# Secondary_Board_2_0.net
KiCad netlist of a schematic drawn in EAGLE
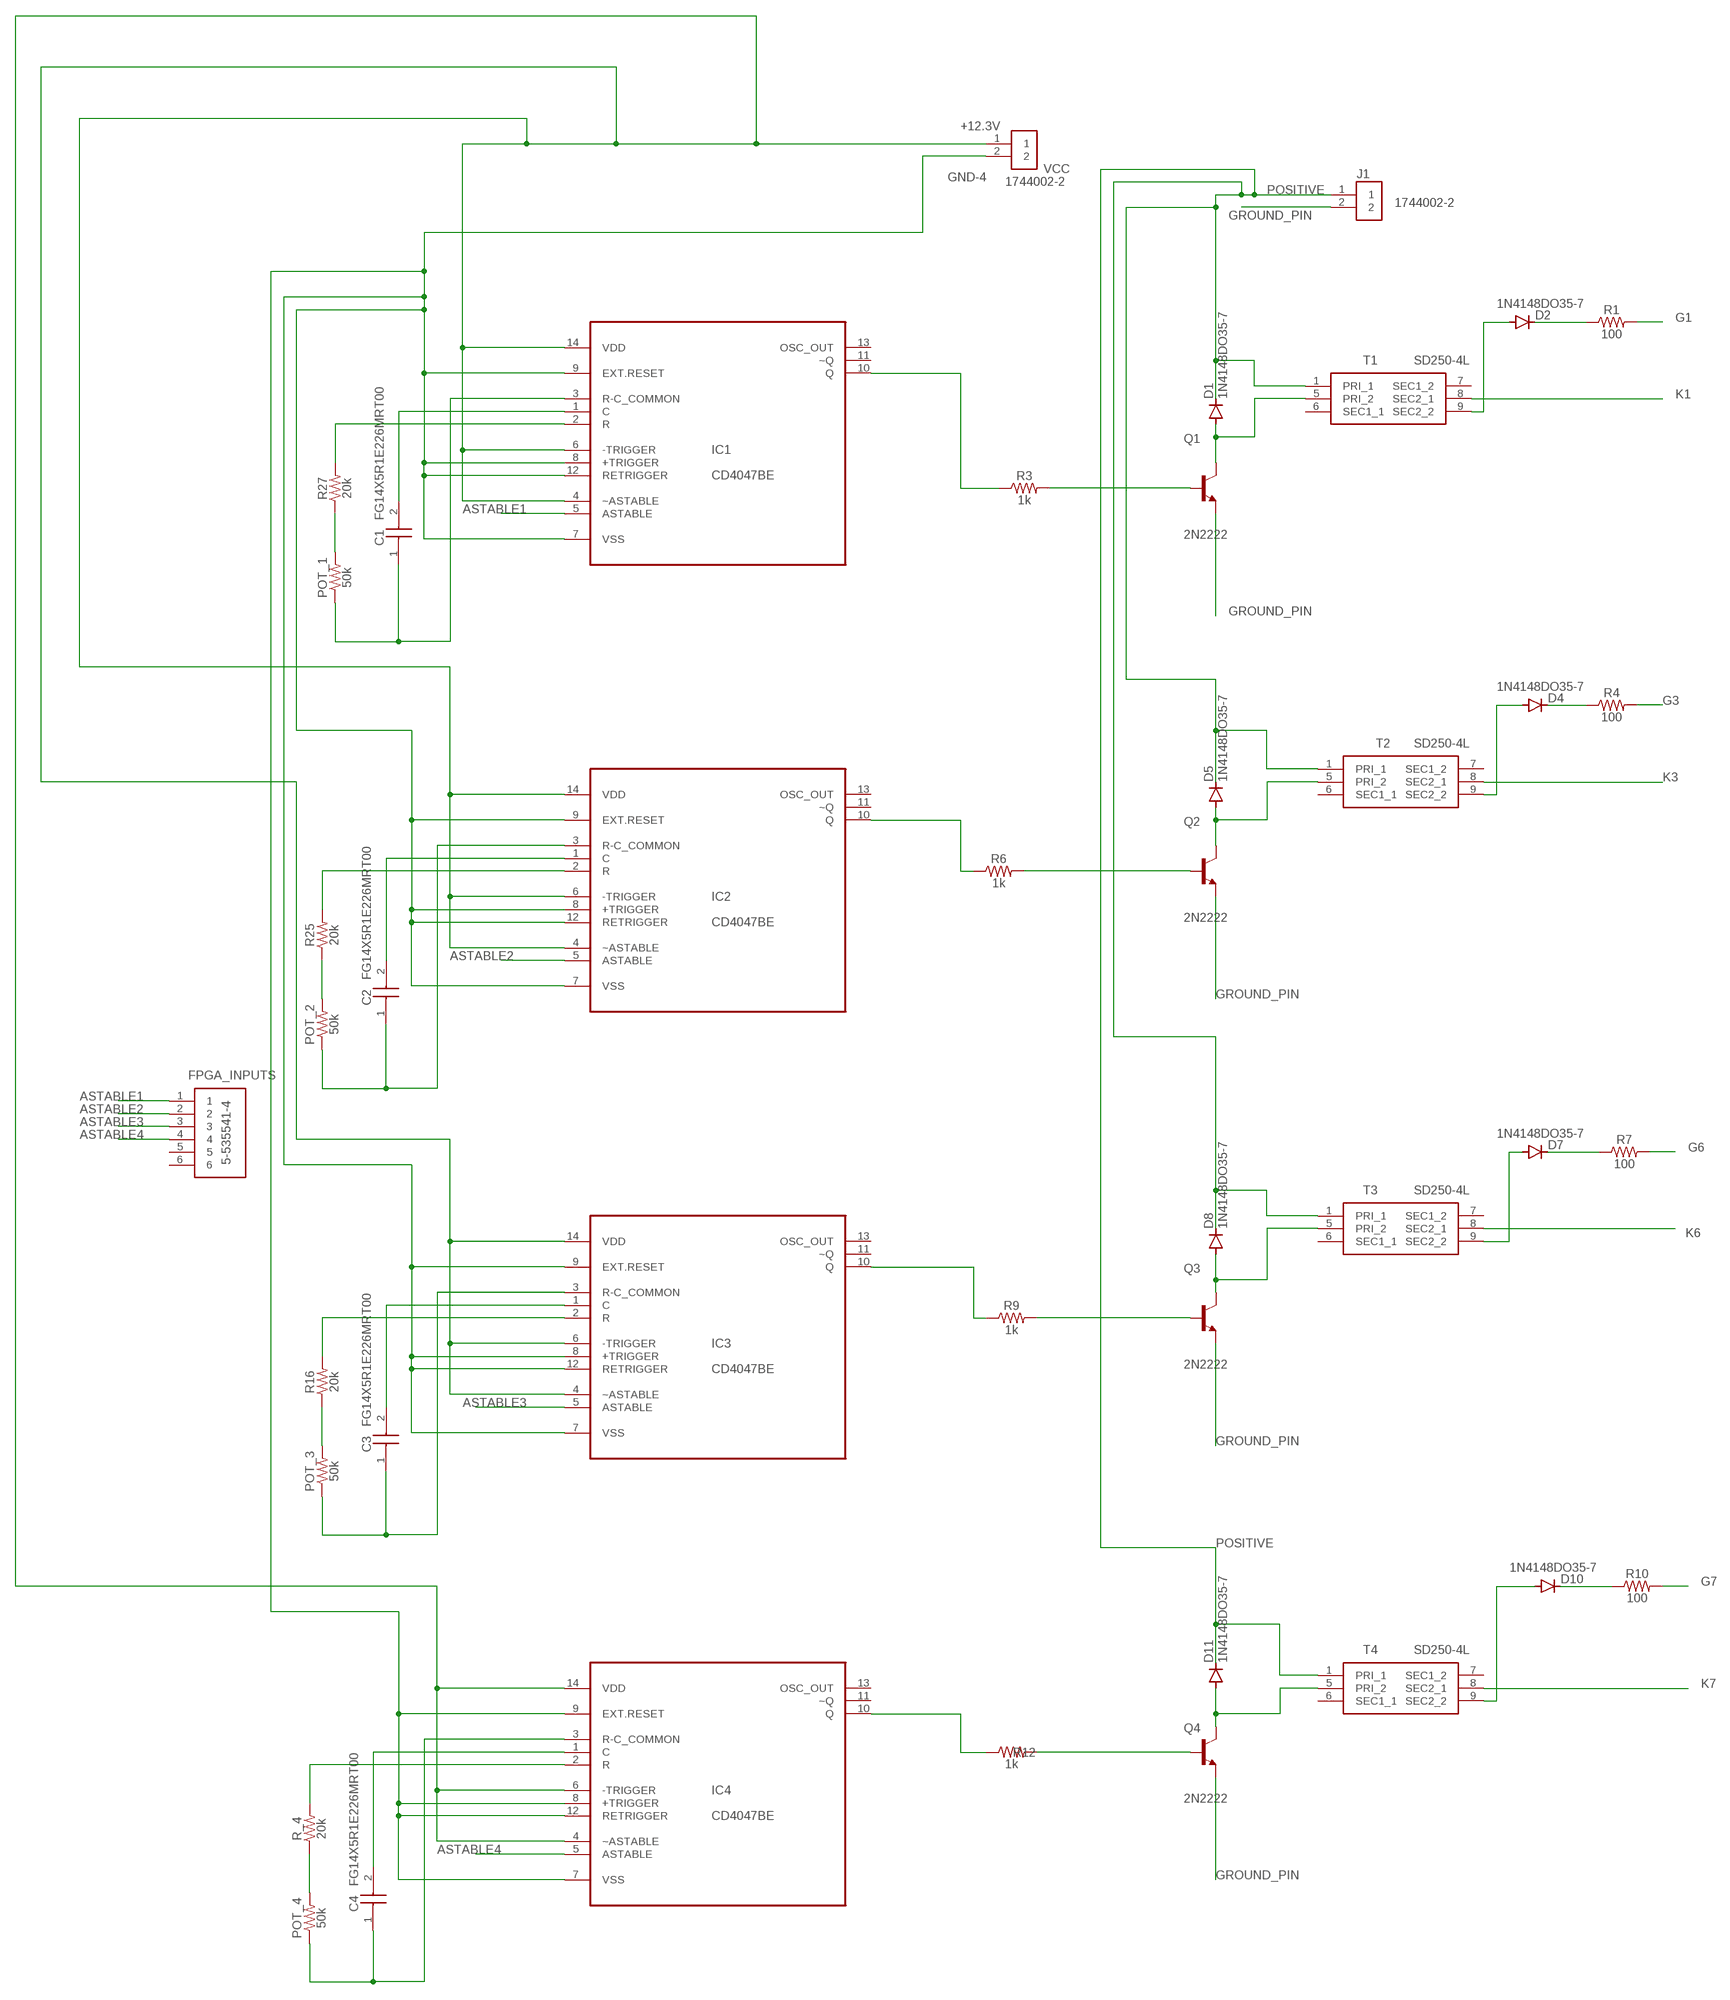
[diagram p0: schematic, sheet 1, part 1 of 2]
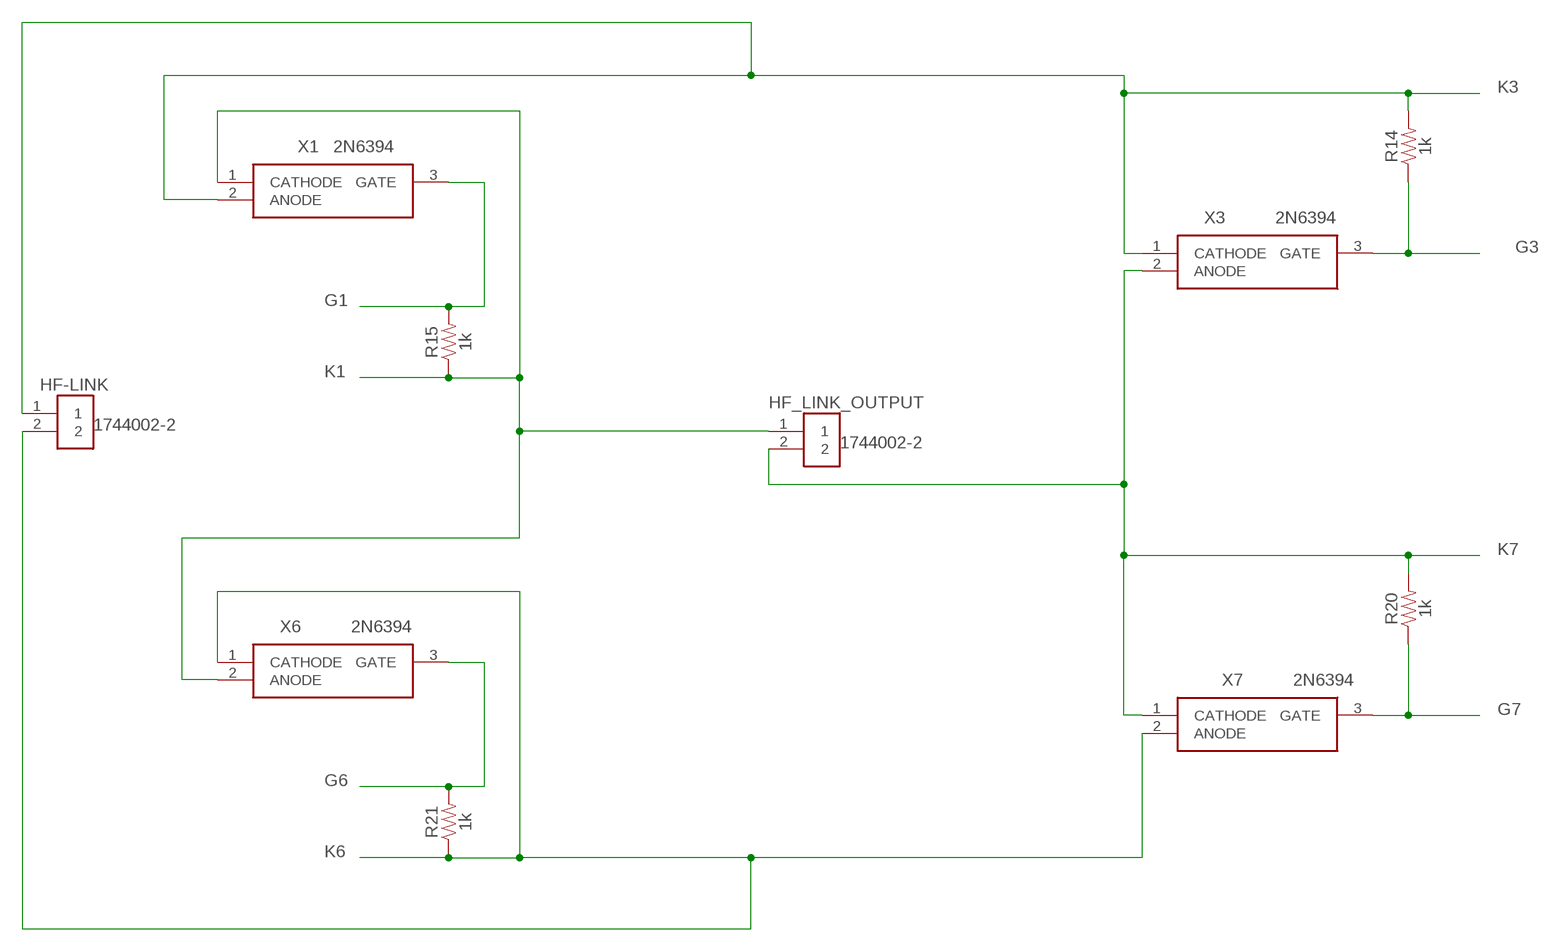
[diagram p1: schematic, sheet 1, part 2 of 2]

(export (version "E")
  (design (tool "Eeschema 10.0.6"))
  (components
    (comp (ref "C1")
      (value "FG14X5R1E226MRT00")
      (footprint "eagle-import:CAPPRD550W50D395H550")
      (libsource (lib "eagle-import") (part "FG14X5R1E226MRT00"))
    )
    (comp (ref "C2")
      (value "FG14X5R1E226MRT00")
      (footprint "eagle-import:CAPPRD550W50D395H550")
      (libsource (lib "eagle-import") (part "FG14X5R1E226MRT00"))
    )
    (comp (ref "C3")
      (value "FG14X5R1E226MRT00")
      (footprint "eagle-import:CAPPRD550W50D395H550")
      (libsource (lib "eagle-import") (part "FG14X5R1E226MRT00"))
    )
    (comp (ref "C4")
      (value "FG14X5R1E226MRT00")
      (footprint "eagle-import:CAPPRD550W50D395H550")
      (libsource (lib "eagle-import") (part "FG14X5R1E226MRT00"))
    )
    (comp (ref "D1")
      (value "1N4148DO35-7")
      (footprint "eagle-import:DO35-7")
      (libsource (lib "eagle-import") (part "1N4148DO35-7"))
    )
    (comp (ref "D2")
      (value "1N4148DO35-7")
      (footprint "eagle-import:DO35-7")
      (libsource (lib "eagle-import") (part "1N4148DO35-7"))
    )
    (comp (ref "D4")
      (value "1N4148DO35-7")
      (footprint "eagle-import:DO35-7")
      (libsource (lib "eagle-import") (part "1N4148DO35-7"))
    )
    (comp (ref "D5")
      (value "1N4148DO35-7")
      (footprint "eagle-import:DO35-7")
      (libsource (lib "eagle-import") (part "1N4148DO35-7"))
    )
    (comp (ref "D7")
      (value "1N4148DO35-7")
      (footprint "eagle-import:DO35-7")
      (libsource (lib "eagle-import") (part "1N4148DO35-7"))
    )
    (comp (ref "D8")
      (value "1N4148DO35-7")
      (footprint "eagle-import:DO35-7")
      (libsource (lib "eagle-import") (part "1N4148DO35-7"))
    )
    (comp (ref "D10")
      (value "1N4148DO35-7")
      (footprint "eagle-import:DO35-7")
      (libsource (lib "eagle-import") (part "1N4148DO35-7"))
    )
    (comp (ref "D11")
      (value "1N4148DO35-7")
      (footprint "eagle-import:DO35-7")
      (libsource (lib "eagle-import") (part "1N4148DO35-7"))
    )
    (comp (ref "FPGA_INPUTS")
      (value "5-535541-4")
      (footprint "eagle-import:SHDR6W76P0X254_1X6_1524X356X62")
      (fields (field (name "MOUSER_PART_NUMBER") "571-5-535541-4"))
      (libsource (lib "eagle-import") (part "5-535541-4"))
    )
    (comp (ref "HF-LINK")
      (value "1744002-2")
      (footprint "eagle-import:CONN_1744002-2")
      (fields (field (name "MF") "TE Connectivity"))
      (libsource (lib "eagle-import") (part "1744002-2"))
    )
    (comp (ref "HF_LINK_OUTPUT")
      (value "1744002-2")
      (footprint "eagle-import:CONN_1744002-2")
      (fields (field (name "MF") "TE Connectivity"))
      (libsource (lib "eagle-import") (part "1744002-2"))
    )
    (comp (ref "IC1")
      (value "CD4047BE")
      (footprint "eagle-import:DIP254P762X508-14")
      (fields (field (name "MF") "Texas Instruments"))
      (libsource (lib "eagle-import") (part "CD4047BE"))
    )
    (comp (ref "IC2")
      (value "CD4047BE")
      (footprint "eagle-import:DIP254P762X508-14")
      (fields (field (name "MF") "Texas Instruments"))
      (libsource (lib "eagle-import") (part "CD4047BE"))
    )
    (comp (ref "IC3")
      (value "CD4047BE")
      (footprint "eagle-import:DIP254P762X508-14")
      (fields (field (name "MF") "Texas Instruments"))
      (libsource (lib "eagle-import") (part "CD4047BE"))
    )
    (comp (ref "IC4")
      (value "CD4047BE")
      (footprint "eagle-import:DIP254P762X508-14")
      (fields (field (name "MF") "Texas Instruments"))
      (libsource (lib "eagle-import") (part "CD4047BE"))
    )
    (comp (ref "J1")
      (value "1744002-2")
      (footprint "eagle-import:CONN_1744002-2")
      (fields (field (name "MF") "TE Connectivity"))
      (libsource (lib "eagle-import") (part "1744002-2"))
    )
    (comp (ref "POT_1")
      (value "50k")
      (footprint "eagle-import:AXIAL-0.3")
      (libsource (lib "eagle-import") (part "1KOHM-HORIZ-1/4W-1%"))
    )
    (comp (ref "POT_2")
      (value "50k")
      (footprint "eagle-import:AXIAL-0.3")
      (libsource (lib "eagle-import") (part "1KOHM-HORIZ-1/4W-1%"))
    )
    (comp (ref "POT_3")
      (value "50k")
      (footprint "eagle-import:AXIAL-0.3")
      (libsource (lib "eagle-import") (part "1KOHM-HORIZ-1/4W-1%"))
    )
    (comp (ref "POT_4")
      (value "50k")
      (footprint "eagle-import:AXIAL-0.3")
      (libsource (lib "eagle-import") (part "1KOHM-HORIZ-1/4W-1%"))
    )
    (comp (ref "Q1")
      (value "2N2222")
      (footprint "eagle-import:TO127P584H533-3")
      (fields (field (name "MF") "Central Semiconductor"))
      (libsource (lib "eagle-import") (part "2N2222"))
    )
    (comp (ref "Q2")
      (value "2N2222")
      (footprint "eagle-import:TO127P584H533-3")
      (fields (field (name "MF") "Central Semiconductor"))
      (libsource (lib "eagle-import") (part "2N2222"))
    )
    (comp (ref "Q3")
      (value "2N2222")
      (footprint "eagle-import:TO127P584H533-3")
      (fields (field (name "MF") "Central Semiconductor"))
      (libsource (lib "eagle-import") (part "2N2222"))
    )
    (comp (ref "Q4")
      (value "2N2222")
      (footprint "eagle-import:TO127P584H533-3")
      (fields (field (name "MF") "Central Semiconductor"))
      (libsource (lib "eagle-import") (part "2N2222"))
    )
    (comp (ref "R1")
      (value "100")
      (footprint "eagle-import:AXIAL-0.3")
      (libsource (lib "eagle-import") (part "100OHM-HORIZ-1/4W-1%"))
    )
    (comp (ref "R3")
      (value "1k")
      (footprint "eagle-import:AXIAL-0.3")
      (libsource (lib "eagle-import") (part "1KOHM-HORIZ-1/4W-1%"))
    )
    (comp (ref "R4")
      (value "100")
      (footprint "eagle-import:AXIAL-0.3")
      (libsource (lib "eagle-import") (part "100OHM-HORIZ-1/4W-1%"))
    )
    (comp (ref "R6")
      (value "1k")
      (footprint "eagle-import:AXIAL-0.3")
      (libsource (lib "eagle-import") (part "1KOHM-HORIZ-1/4W-1%"))
    )
    (comp (ref "R7")
      (value "100")
      (footprint "eagle-import:AXIAL-0.3")
      (libsource (lib "eagle-import") (part "100OHM-HORIZ-1/4W-1%"))
    )
    (comp (ref "R9")
      (value "1k")
      (footprint "eagle-import:AXIAL-0.3")
      (libsource (lib "eagle-import") (part "1KOHM-HORIZ-1/4W-1%"))
    )
    (comp (ref "R10")
      (value "100")
      (footprint "eagle-import:AXIAL-0.3")
      (libsource (lib "eagle-import") (part "100OHM-HORIZ-1/4W-1%"))
    )
    (comp (ref "R12")
      (value "1k")
      (footprint "eagle-import:AXIAL-0.3")
      (libsource (lib "eagle-import") (part "1KOHM-HORIZ-1/4W-1%"))
    )
    (comp (ref "R14")
      (value "1k")
      (footprint "eagle-import:AXIAL-0.3")
      (libsource (lib "eagle-import") (part "1KOHM-HORIZ-1/4W-1%"))
    )
    (comp (ref "R15")
      (value "1k")
      (footprint "eagle-import:AXIAL-0.3")
      (libsource (lib "eagle-import") (part "1KOHM-HORIZ-1/4W-1%"))
    )
    (comp (ref "R16")
      (value "20k")
      (footprint "eagle-import:AXIAL-0.3")
      (libsource (lib "eagle-import") (part "1KOHM-HORIZ-1/4W-1%"))
    )
    (comp (ref "R20")
      (value "1k")
      (footprint "eagle-import:AXIAL-0.3")
      (libsource (lib "eagle-import") (part "1KOHM-HORIZ-1/4W-1%"))
    )
    (comp (ref "R21")
      (value "1k")
      (footprint "eagle-import:AXIAL-0.3")
      (libsource (lib "eagle-import") (part "1KOHM-HORIZ-1/4W-1%"))
    )
    (comp (ref "R25")
      (value "20k")
      (footprint "eagle-import:AXIAL-0.3")
      (libsource (lib "eagle-import") (part "1KOHM-HORIZ-1/4W-1%"))
    )
    (comp (ref "R27")
      (value "20k")
      (footprint "eagle-import:AXIAL-0.3")
      (libsource (lib "eagle-import") (part "1KOHM-HORIZ-1/4W-1%"))
    )
    (comp (ref "R_4")
      (value "20k")
      (footprint "eagle-import:AXIAL-0.3")
      (libsource (lib "eagle-import") (part "1KOHM-HORIZ-1/4W-1%"))
    )
    (comp (ref "T1")
      (value "SD250-4L")
      (footprint "eagle-import:SD2504L")
      (libsource (lib "eagle-import") (part "SD250-4L"))
    )
    (comp (ref "T2")
      (value "SD250-4L")
      (footprint "eagle-import:SD2504L")
      (libsource (lib "eagle-import") (part "SD250-4L"))
    )
    (comp (ref "T3")
      (value "SD250-4L")
      (footprint "eagle-import:SD2504L")
      (libsource (lib "eagle-import") (part "SD250-4L"))
    )
    (comp (ref "T4")
      (value "SD250-4L")
      (footprint "eagle-import:SD2504L")
      (libsource (lib "eagle-import") (part "SD250-4L"))
    )
    (comp (ref "VCC")
      (value "1744002-2")
      (footprint "eagle-import:CONN_1744002-2")
      (fields (field (name "MF") "TE Connectivity"))
      (libsource (lib "eagle-import") (part "1744002-2"))
    )
    (comp (ref "X1")
      (value "2N6394")
      (footprint "eagle-import:TO254P482X997X2018-3P")
      (fields (field (name "MOUSER_PART_NUMBER") "863-2N6394"))
      (libsource (lib "eagle-import") (part "2N6394"))
    )
    (comp (ref "X3")
      (value "2N6394")
      (footprint "eagle-import:TO254P482X997X2018-3P")
      (fields (field (name "MOUSER_PART_NUMBER") "863-2N6394"))
      (libsource (lib "eagle-import") (part "2N6394"))
    )
    (comp (ref "X6")
      (value "2N6394")
      (footprint "eagle-import:TO254P482X997X2018-3P")
      (fields (field (name "MOUSER_PART_NUMBER") "863-2N6394"))
      (libsource (lib "eagle-import") (part "2N6394"))
    )
    (comp (ref "X7")
      (value "2N6394")
      (footprint "eagle-import:TO254P482X997X2018-3P")
      (fields (field (name "MOUSER_PART_NUMBER") "863-2N6394"))
      (libsource (lib "eagle-import") (part "2N6394"))
    )
  )
  (nets
    (net (code "1") (name "/+12.3V") (class "Default")
      (node (ref "IC1") (pin "14") (pinfunction "VDD_14") (pintype "power_in"))
      (node (ref "IC1") (pin "4") (pinfunction "~{ASTABLE}_4") (pintype "input"))
      (node (ref "IC1") (pin "6") (pinfunction "-TRIGGER_6") (pintype "power_in"))
      (node (ref "IC2") (pin "14") (pinfunction "VDD_14") (pintype "power_in"))
      (node (ref "IC2") (pin "4") (pinfunction "~{ASTABLE}_4") (pintype "input"))
      (node (ref "IC2") (pin "6") (pinfunction "-TRIGGER_6") (pintype "power_in"))
      (node (ref "IC3") (pin "14") (pinfunction "VDD_14") (pintype "power_in"))
      (node (ref "IC3") (pin "4") (pinfunction "~{ASTABLE}_4") (pintype "input"))
      (node (ref "IC3") (pin "6") (pinfunction "-TRIGGER_6") (pintype "power_in"))
      (node (ref "IC4") (pin "14") (pinfunction "VDD_14") (pintype "power_in"))
      (node (ref "IC4") (pin "4") (pinfunction "~{ASTABLE}_4") (pintype "input"))
      (node (ref "IC4") (pin "6") (pinfunction "-TRIGGER_6") (pintype "power_in"))
      (node (ref "VCC") (pin "1") (pinfunction "1_1") (pintype "passive"))
    )
    (net (code "2") (name "/ASTABLE1") (class "Default")
      (node (ref "FPGA_INPUTS") (pin "1") (pinfunction "1_1") (pintype "bidirectional"))
      (node (ref "IC1") (pin "5") (pinfunction "ASTABLE_5") (pintype "input"))
    )
    (net (code "3") (name "/ASTABLE2") (class "Default")
      (node (ref "FPGA_INPUTS") (pin "2") (pinfunction "2_2") (pintype "bidirectional"))
      (node (ref "IC2") (pin "5") (pinfunction "ASTABLE_5") (pintype "input"))
    )
    (net (code "4") (name "/ASTABLE3") (class "Default")
      (node (ref "FPGA_INPUTS") (pin "3") (pinfunction "3_3") (pintype "bidirectional"))
      (node (ref "IC3") (pin "5") (pinfunction "ASTABLE_5") (pintype "input"))
    )
    (net (code "5") (name "/ASTABLE4") (class "Default")
      (node (ref "FPGA_INPUTS") (pin "4") (pinfunction "4_4") (pintype "bidirectional"))
      (node (ref "IC4") (pin "5") (pinfunction "ASTABLE_5") (pintype "input"))
    )
    (net (code "6") (name "/G1") (class "Default")
      (node (ref "R1") (pin "P$2") (pinfunction "2_P$2") (pintype "passive"))
      (node (ref "R15") (pin "P$2") (pinfunction "2_P$2") (pintype "passive"))
      (node (ref "X1") (pin "3") (pinfunction "GATE_3") (pintype "bidirectional"))
    )
    (net (code "7") (name "/G3") (class "Default")
      (node (ref "R14") (pin "P$1") (pinfunction "1_P$1") (pintype "passive"))
      (node (ref "R4") (pin "P$2") (pinfunction "2_P$2") (pintype "passive"))
      (node (ref "X3") (pin "3") (pinfunction "GATE_3") (pintype "bidirectional"))
    )
    (net (code "8") (name "/G6") (class "Default")
      (node (ref "R21") (pin "P$2") (pinfunction "2_P$2") (pintype "passive"))
      (node (ref "R7") (pin "P$2") (pinfunction "2_P$2") (pintype "passive"))
      (node (ref "X6") (pin "3") (pinfunction "GATE_3") (pintype "bidirectional"))
    )
    (net (code "9") (name "/G7") (class "Default")
      (node (ref "R10") (pin "P$2") (pinfunction "2_P$2") (pintype "passive"))
      (node (ref "R20") (pin "P$1") (pinfunction "1_P$1") (pintype "passive"))
      (node (ref "X7") (pin "3") (pinfunction "GATE_3") (pintype "bidirectional"))
    )
    (net (code "10") (name "/GND-4") (class "Default")
      (node (ref "IC1") (pin "12") (pinfunction "RETRIGGER_12") (pintype "input"))
      (node (ref "IC1") (pin "7") (pinfunction "VSS_7") (pintype "power_in"))
      (node (ref "IC1") (pin "8") (pinfunction "+TRIGGER_8") (pintype "input"))
      (node (ref "IC1") (pin "9") (pinfunction "EXT.RESET_9") (pintype "input"))
      (node (ref "IC2") (pin "12") (pinfunction "RETRIGGER_12") (pintype "input"))
      (node (ref "IC2") (pin "7") (pinfunction "VSS_7") (pintype "power_in"))
      (node (ref "IC2") (pin "8") (pinfunction "+TRIGGER_8") (pintype "input"))
      (node (ref "IC2") (pin "9") (pinfunction "EXT.RESET_9") (pintype "input"))
      (node (ref "IC3") (pin "12") (pinfunction "RETRIGGER_12") (pintype "input"))
      (node (ref "IC3") (pin "7") (pinfunction "VSS_7") (pintype "power_in"))
      (node (ref "IC3") (pin "8") (pinfunction "+TRIGGER_8") (pintype "input"))
      (node (ref "IC3") (pin "9") (pinfunction "EXT.RESET_9") (pintype "input"))
      (node (ref "IC4") (pin "12") (pinfunction "RETRIGGER_12") (pintype "input"))
      (node (ref "IC4") (pin "7") (pinfunction "VSS_7") (pintype "power_in"))
      (node (ref "IC4") (pin "8") (pinfunction "+TRIGGER_8") (pintype "input"))
      (node (ref "IC4") (pin "9") (pinfunction "EXT.RESET_9") (pintype "input"))
      (node (ref "VCC") (pin "2") (pinfunction "2_2") (pintype "passive"))
    )
    (net (code "11") (name "/GROUND_PIN") (class "Default")
      (node (ref "J1") (pin "2") (pinfunction "2_2") (pintype "passive"))
      (node (ref "Q1") (pin "1") (pinfunction "E_1") (pintype "passive"))
      (node (ref "Q2") (pin "1") (pinfunction "E_1") (pintype "passive"))
      (node (ref "Q3") (pin "1") (pinfunction "E_1") (pintype "passive"))
      (node (ref "Q4") (pin "1") (pinfunction "E_1") (pintype "passive"))
    )
    (net (code "12") (name "/K1") (class "Default")
      (node (ref "HF_LINK_OUTPUT") (pin "1") (pinfunction "1_1") (pintype "passive"))
      (node (ref "R15") (pin "P$1") (pinfunction "1_P$1") (pintype "passive"))
      (node (ref "T1") (pin "8") (pinfunction "SEC2_1_8") (pintype "bidirectional"))
      (node (ref "X1") (pin "1") (pinfunction "CATHODE_1") (pintype "bidirectional"))
      (node (ref "X6") (pin "2") (pinfunction "ANODE_2") (pintype "bidirectional"))
    )
    (net (code "13") (name "/K3") (class "Default")
      (node (ref "HF-LINK") (pin "1") (pinfunction "1_1") (pintype "passive"))
      (node (ref "R14") (pin "P$2") (pinfunction "2_P$2") (pintype "passive"))
      (node (ref "T2") (pin "8") (pinfunction "SEC2_1_8") (pintype "bidirectional"))
      (node (ref "X1") (pin "2") (pinfunction "ANODE_2") (pintype "bidirectional"))
      (node (ref "X3") (pin "1") (pinfunction "CATHODE_1") (pintype "bidirectional"))
    )
    (net (code "14") (name "/K6") (class "Default")
      (node (ref "HF-LINK") (pin "2") (pinfunction "2_2") (pintype "passive"))
      (node (ref "R21") (pin "P$1") (pinfunction "1_P$1") (pintype "passive"))
      (node (ref "T3") (pin "8") (pinfunction "SEC2_1_8") (pintype "bidirectional"))
      (node (ref "X6") (pin "1") (pinfunction "CATHODE_1") (pintype "bidirectional"))
      (node (ref "X7") (pin "2") (pinfunction "ANODE_2") (pintype "bidirectional"))
    )
    (net (code "15") (name "/K7") (class "Default")
      (node (ref "HF_LINK_OUTPUT") (pin "2") (pinfunction "2_2") (pintype "passive"))
      (node (ref "R20") (pin "P$2") (pinfunction "2_P$2") (pintype "passive"))
      (node (ref "T4") (pin "8") (pinfunction "SEC2_1_8") (pintype "bidirectional"))
      (node (ref "X3") (pin "2") (pinfunction "ANODE_2") (pintype "bidirectional"))
      (node (ref "X7") (pin "1") (pinfunction "CATHODE_1") (pintype "bidirectional"))
    )
    (net (code "16") (name "/POSITIVE") (class "Default")
      (node (ref "D1") (pin "C") (pinfunction "C_C") (pintype "passive"))
      (node (ref "D11") (pin "C") (pinfunction "C_C") (pintype "passive"))
      (node (ref "D5") (pin "C") (pinfunction "C_C") (pintype "passive"))
      (node (ref "D8") (pin "C") (pinfunction "C_C") (pintype "passive"))
      (node (ref "J1") (pin "1") (pinfunction "1_1") (pintype "passive"))
      (node (ref "T1") (pin "1") (pinfunction "PRI_1_1") (pintype "bidirectional"))
      (node (ref "T2") (pin "1") (pinfunction "PRI_1_1") (pintype "bidirectional"))
      (node (ref "T3") (pin "1") (pinfunction "PRI_1_1") (pintype "bidirectional"))
      (node (ref "T4") (pin "1") (pinfunction "PRI_1_1") (pintype "bidirectional"))
    )
    (net (code "17") (name "Net-(C1-+)") (class "Default")
      (node (ref "C1") (pin "1") (pinfunction "+_1") (pintype "bidirectional"))
      (node (ref "IC1") (pin "3") (pinfunction "R-C_COMMON_3") (pintype "input"))
      (node (ref "POT_1") (pin "P$1") (pinfunction "1_P$1") (pintype "passive"))
    )
    (net (code "18") (name "Net-(C1--)") (class "Default")
      (node (ref "C1") (pin "2") (pinfunction "-_2") (pintype "bidirectional"))
      (node (ref "IC1") (pin "1") (pinfunction "C_1") (pintype "input"))
    )
    (net (code "19") (name "Net-(C2-+)") (class "Default")
      (node (ref "C2") (pin "1") (pinfunction "+_1") (pintype "bidirectional"))
      (node (ref "IC2") (pin "3") (pinfunction "R-C_COMMON_3") (pintype "input"))
      (node (ref "POT_2") (pin "P$1") (pinfunction "1_P$1") (pintype "passive"))
    )
    (net (code "20") (name "Net-(C2--)") (class "Default")
      (node (ref "C2") (pin "2") (pinfunction "-_2") (pintype "bidirectional"))
      (node (ref "IC2") (pin "1") (pinfunction "C_1") (pintype "input"))
    )
    (net (code "21") (name "Net-(C3-+)") (class "Default")
      (node (ref "C3") (pin "1") (pinfunction "+_1") (pintype "bidirectional"))
      (node (ref "IC3") (pin "3") (pinfunction "R-C_COMMON_3") (pintype "input"))
      (node (ref "POT_3") (pin "P$1") (pinfunction "1_P$1") (pintype "passive"))
    )
    (net (code "22") (name "Net-(C3--)") (class "Default")
      (node (ref "C3") (pin "2") (pinfunction "-_2") (pintype "bidirectional"))
      (node (ref "IC3") (pin "1") (pinfunction "C_1") (pintype "input"))
    )
    (net (code "23") (name "Net-(C4-+)") (class "Default")
      (node (ref "C4") (pin "1") (pinfunction "+_1") (pintype "bidirectional"))
      (node (ref "IC4") (pin "3") (pinfunction "R-C_COMMON_3") (pintype "input"))
      (node (ref "POT_4") (pin "P$1") (pinfunction "1_P$1") (pintype "passive"))
    )
    (net (code "24") (name "Net-(C4--)") (class "Default")
      (node (ref "C4") (pin "2") (pinfunction "-_2") (pintype "bidirectional"))
      (node (ref "IC4") (pin "1") (pinfunction "C_1") (pintype "input"))
    )
    (net (code "25") (name "Net-(IC1-Q)") (class "Default")
      (node (ref "IC1") (pin "10") (pinfunction "Q_10") (pintype "output"))
      (node (ref "R3") (pin "P$1") (pinfunction "1_P$1") (pintype "passive"))
    )
    (net (code "26") (name "Net-(IC1-R)") (class "Default")
      (node (ref "IC1") (pin "2") (pinfunction "R_2") (pintype "input"))
      (node (ref "R27") (pin "P$2") (pinfunction "2_P$2") (pintype "passive"))
    )
    (net (code "27") (name "Net-(IC2-Q)") (class "Default")
      (node (ref "IC2") (pin "10") (pinfunction "Q_10") (pintype "output"))
      (node (ref "R6") (pin "P$1") (pinfunction "1_P$1") (pintype "passive"))
    )
    (net (code "28") (name "Net-(IC2-R)") (class "Default")
      (node (ref "IC2") (pin "2") (pinfunction "R_2") (pintype "input"))
      (node (ref "R25") (pin "P$2") (pinfunction "2_P$2") (pintype "passive"))
    )
    (net (code "29") (name "Net-(IC3-Q)") (class "Default")
      (node (ref "IC3") (pin "10") (pinfunction "Q_10") (pintype "output"))
      (node (ref "R9") (pin "P$1") (pinfunction "1_P$1") (pintype "passive"))
    )
    (net (code "30") (name "Net-(IC3-R)") (class "Default")
      (node (ref "IC3") (pin "2") (pinfunction "R_2") (pintype "input"))
      (node (ref "R16") (pin "P$2") (pinfunction "2_P$2") (pintype "passive"))
    )
    (net (code "31") (name "Net-(IC4-Q)") (class "Default")
      (node (ref "IC4") (pin "10") (pinfunction "Q_10") (pintype "output"))
      (node (ref "R12") (pin "P$1") (pinfunction "1_P$1") (pintype "passive"))
    )
    (net (code "32") (name "Net-(IC4-R)") (class "Default")
      (node (ref "IC4") (pin "2") (pinfunction "R_2") (pintype "input"))
      (node (ref "R_4") (pin "P$2") (pinfunction "2_P$2") (pintype "passive"))
    )
    (net (code "33") (name "Net-(POT_1-2)") (class "Default")
      (node (ref "POT_1") (pin "P$2") (pinfunction "2_P$2") (pintype "passive"))
      (node (ref "R27") (pin "P$1") (pinfunction "1_P$1") (pintype "passive"))
    )
    (net (code "34") (name "Net-(POT_2-2)") (class "Default")
      (node (ref "POT_2") (pin "P$2") (pinfunction "2_P$2") (pintype "passive"))
      (node (ref "R25") (pin "P$1") (pinfunction "1_P$1") (pintype "passive"))
    )
    (net (code "35") (name "Net-(POT_3-2)") (class "Default")
      (node (ref "POT_3") (pin "P$2") (pinfunction "2_P$2") (pintype "passive"))
      (node (ref "R16") (pin "P$1") (pinfunction "1_P$1") (pintype "passive"))
    )
    (net (code "36") (name "Net-(POT_4-2)") (class "Default")
      (node (ref "POT_4") (pin "P$2") (pinfunction "2_P$2") (pintype "passive"))
      (node (ref "R_4") (pin "P$1") (pinfunction "1_P$1") (pintype "passive"))
    )
    (net (code "37") (name "Net-(Q1-B)") (class "Default")
      (node (ref "Q1") (pin "2") (pinfunction "B_2") (pintype "passive"))
      (node (ref "R3") (pin "P$2") (pinfunction "2_P$2") (pintype "passive"))
    )
    (net (code "38") (name "Net-(Q1-C)") (class "Default")
      (node (ref "D1") (pin "A") (pinfunction "A_A") (pintype "passive"))
      (node (ref "Q1") (pin "3") (pinfunction "C_3") (pintype "passive"))
      (node (ref "T1") (pin "5") (pinfunction "PRI_2_5") (pintype "bidirectional"))
    )
    (net (code "39") (name "Net-(Q2-B)") (class "Default")
      (node (ref "Q2") (pin "2") (pinfunction "B_2") (pintype "passive"))
      (node (ref "R6") (pin "P$2") (pinfunction "2_P$2") (pintype "passive"))
    )
    (net (code "40") (name "Net-(Q2-C)") (class "Default")
      (node (ref "D5") (pin "A") (pinfunction "A_A") (pintype "passive"))
      (node (ref "Q2") (pin "3") (pinfunction "C_3") (pintype "passive"))
      (node (ref "T2") (pin "5") (pinfunction "PRI_2_5") (pintype "bidirectional"))
    )
    (net (code "41") (name "Net-(Q3-B)") (class "Default")
      (node (ref "Q3") (pin "2") (pinfunction "B_2") (pintype "passive"))
      (node (ref "R9") (pin "P$2") (pinfunction "2_P$2") (pintype "passive"))
    )
    (net (code "42") (name "Net-(Q3-C)") (class "Default")
      (node (ref "D8") (pin "A") (pinfunction "A_A") (pintype "passive"))
      (node (ref "Q3") (pin "3") (pinfunction "C_3") (pintype "passive"))
      (node (ref "T3") (pin "5") (pinfunction "PRI_2_5") (pintype "bidirectional"))
    )
    (net (code "43") (name "Net-(Q4-B)") (class "Default")
      (node (ref "Q4") (pin "2") (pinfunction "B_2") (pintype "passive"))
      (node (ref "R12") (pin "P$2") (pinfunction "2_P$2") (pintype "passive"))
    )
    (net (code "44") (name "Net-(Q4-C)") (class "Default")
      (node (ref "D11") (pin "A") (pinfunction "A_A") (pintype "passive"))
      (node (ref "Q4") (pin "3") (pinfunction "C_3") (pintype "passive"))
      (node (ref "T4") (pin "5") (pinfunction "PRI_2_5") (pintype "bidirectional"))
    )
    (net (code "45") (name "Net-(R1-1)") (class "Default")
      (node (ref "D2") (pin "C") (pinfunction "C_C") (pintype "passive"))
      (node (ref "R1") (pin "P$1") (pinfunction "1_P$1") (pintype "passive"))
    )
    (net (code "46") (name "Net-(R4-1)") (class "Default")
      (node (ref "D4") (pin "C") (pinfunction "C_C") (pintype "passive"))
      (node (ref "R4") (pin "P$1") (pinfunction "1_P$1") (pintype "passive"))
    )
    (net (code "47") (name "Net-(R7-1)") (class "Default")
      (node (ref "D7") (pin "C") (pinfunction "C_C") (pintype "passive"))
      (node (ref "R7") (pin "P$1") (pinfunction "1_P$1") (pintype "passive"))
    )
    (net (code "48") (name "Net-(R10-1)") (class "Default")
      (node (ref "D10") (pin "C") (pinfunction "C_C") (pintype "passive"))
      (node (ref "R10") (pin "P$1") (pinfunction "1_P$1") (pintype "passive"))
    )
    (net (code "49") (name "Net-(T1-SEC2_2)") (class "Default")
      (node (ref "D2") (pin "A") (pinfunction "A_A") (pintype "passive"))
      (node (ref "T1") (pin "9") (pinfunction "SEC2_2_9") (pintype "bidirectional"))
    )
    (net (code "50") (name "Net-(T2-SEC2_2)") (class "Default")
      (node (ref "D4") (pin "A") (pinfunction "A_A") (pintype "passive"))
      (node (ref "T2") (pin "9") (pinfunction "SEC2_2_9") (pintype "bidirectional"))
    )
    (net (code "51") (name "Net-(T3-SEC2_2)") (class "Default")
      (node (ref "D7") (pin "A") (pinfunction "A_A") (pintype "passive"))
      (node (ref "T3") (pin "9") (pinfunction "SEC2_2_9") (pintype "bidirectional"))
    )
    (net (code "52") (name "Net-(T4-SEC2_2)") (class "Default")
      (node (ref "D10") (pin "A") (pinfunction "A_A") (pintype "passive"))
      (node (ref "T4") (pin "9") (pinfunction "SEC2_2_9") (pintype "bidirectional"))
    )
    (net (code "53") (name "unconnected-(FPGA_INPUTS-Pad5)") (class "Default")
      (node (ref "FPGA_INPUTS") (pin "5") (pinfunction "5_5") (pintype "bidirectional"))
    )
    (net (code "54") (name "unconnected-(FPGA_INPUTS-Pad6)") (class "Default")
      (node (ref "FPGA_INPUTS") (pin "6") (pinfunction "6_6") (pintype "bidirectional"))
    )
    (net (code "55") (name "unconnected-(IC1-OSC_OUT-Pad13)") (class "Default")
      (node (ref "IC1") (pin "13") (pinfunction "OSC_OUT_13") (pintype "output"))
    )
    (net (code "56") (name "unconnected-(IC1-~{Q}-Pad11)") (class "Default")
      (node (ref "IC1") (pin "11") (pinfunction "~{Q}_11") (pintype "output"))
    )
    (net (code "57") (name "unconnected-(IC2-OSC_OUT-Pad13)") (class "Default")
      (node (ref "IC2") (pin "13") (pinfunction "OSC_OUT_13") (pintype "output"))
    )
    (net (code "58") (name "unconnected-(IC2-~{Q}-Pad11)") (class "Default")
      (node (ref "IC2") (pin "11") (pinfunction "~{Q}_11") (pintype "output"))
    )
    (net (code "59") (name "unconnected-(IC3-OSC_OUT-Pad13)") (class "Default")
      (node (ref "IC3") (pin "13") (pinfunction "OSC_OUT_13") (pintype "output"))
    )
    (net (code "60") (name "unconnected-(IC3-~{Q}-Pad11)") (class "Default")
      (node (ref "IC3") (pin "11") (pinfunction "~{Q}_11") (pintype "output"))
    )
    (net (code "61") (name "unconnected-(IC4-OSC_OUT-Pad13)") (class "Default")
      (node (ref "IC4") (pin "13") (pinfunction "OSC_OUT_13") (pintype "output"))
    )
    (net (code "62") (name "unconnected-(IC4-~{Q}-Pad11)") (class "Default")
      (node (ref "IC4") (pin "11") (pinfunction "~{Q}_11") (pintype "output"))
    )
    (net (code "63") (name "unconnected-(T1-SEC1_1-Pad6)") (class "Default")
      (node (ref "T1") (pin "6") (pinfunction "SEC1_1_6") (pintype "bidirectional"))
    )
    (net (code "64") (name "unconnected-(T1-SEC1_2-Pad7)") (class "Default")
      (node (ref "T1") (pin "7") (pinfunction "SEC1_2_7") (pintype "bidirectional"))
    )
    (net (code "65") (name "unconnected-(T2-SEC1_1-Pad6)") (class "Default")
      (node (ref "T2") (pin "6") (pinfunction "SEC1_1_6") (pintype "bidirectional"))
    )
    (net (code "66") (name "unconnected-(T2-SEC1_2-Pad7)") (class "Default")
      (node (ref "T2") (pin "7") (pinfunction "SEC1_2_7") (pintype "bidirectional"))
    )
    (net (code "67") (name "unconnected-(T3-SEC1_1-Pad6)") (class "Default")
      (node (ref "T3") (pin "6") (pinfunction "SEC1_1_6") (pintype "bidirectional"))
    )
    (net (code "68") (name "unconnected-(T3-SEC1_2-Pad7)") (class "Default")
      (node (ref "T3") (pin "7") (pinfunction "SEC1_2_7") (pintype "bidirectional"))
    )
    (net (code "69") (name "unconnected-(T4-SEC1_1-Pad6)") (class "Default")
      (node (ref "T4") (pin "6") (pinfunction "SEC1_1_6") (pintype "bidirectional"))
    )
    (net (code "70") (name "unconnected-(T4-SEC1_2-Pad7)") (class "Default")
      (node (ref "T4") (pin "7") (pinfunction "SEC1_2_7") (pintype "bidirectional"))
    )
  )
)
